# Ampli.net
KiCad netlist of a schematic drawn in Altium Designer
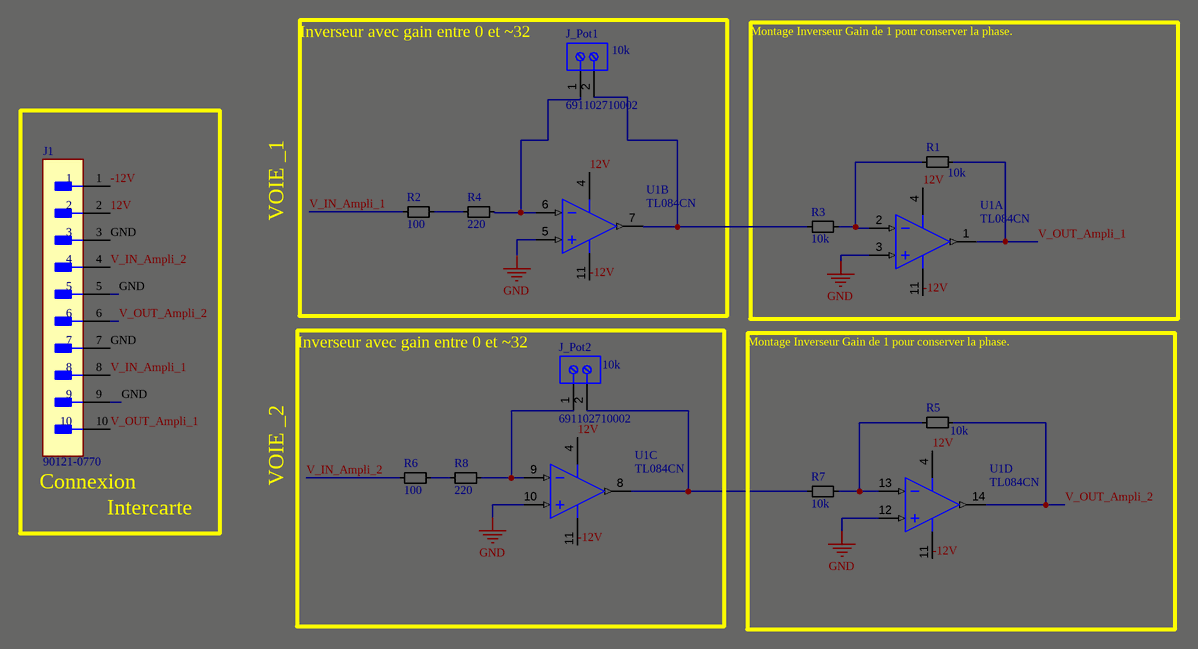
[diagram p0: Ampli.SchDoc]

(export (version "E")
  (design (tool "Eeschema 10.0.6"))
  (components
    (comp (ref "J1")
      (value "90121-0770")
      (footprint "FP-90121-0770-MFG")
      (description "CONN HEADER R/A 10POS 2.54MM")
      (libsource (lib "Altium Content Vault") (part "aee40dc8b284c03a16094555aa210be"))
    )
    (comp (ref "J_Pot1")
      (value "691102710002")
      (footprint "691102710002")
      (fields (field (name "VOLTAGE") "300V"))
      (libsource (lib "Altium Content Vault") (part "TBL - 1R - 02P - Screw"))
    )
    (comp (ref "J_Pot2")
      (value "691102710002")
      (footprint "691102710002")
      (fields (field (name "VOLTAGE") "300V"))
      (libsource (lib "Altium Content Vault") (part "TBL - 1R - 02P - Screw"))
    )
    (comp (ref "R1")
      (value "10k")
      (footprint "PCB:Res_Axial_3.5x6.5mm_TH")
      (fields (field (name "Comment") "Res_3.5x6.5mm_TH"))
      (libsource (lib "Schema") (part "Res_3.5x6.5mm_TH"))
    )
    (comp (ref "R2")
      (value "100")
      (footprint "PCB:Res_Axial_3.5x6.5mm_TH")
      (fields (field (name "Comment") "Res_3.5x6.5mm_TH"))
      (libsource (lib "Schema") (part "Res_3.5x6.5mm_TH"))
    )
    (comp (ref "R3")
      (value "10k")
      (footprint "PCB:Res_Axial_3.5x6.5mm_TH")
      (fields (field (name "Comment") "Res_3.5x6.5mm_TH"))
      (libsource (lib "Schema") (part "Res_3.5x6.5mm_TH"))
    )
    (comp (ref "R4")
      (value "220")
      (footprint "PCB:Res_Axial_3.5x6.5mm_TH")
      (fields (field (name "Comment") "Res_3.5x6.5mm_TH"))
      (libsource (lib "Schema") (part "Res_3.5x6.5mm_TH"))
    )
    (comp (ref "R5")
      (value "10k")
      (footprint "PCB:Res_Axial_3.5x6.5mm_TH")
      (fields (field (name "Comment") "Res_3.5x6.5mm_TH"))
      (libsource (lib "Schema") (part "Res_3.5x6.5mm_TH"))
    )
    (comp (ref "R6")
      (value "100")
      (footprint "PCB:Res_Axial_3.5x6.5mm_TH")
      (fields (field (name "Comment") "Res_3.5x6.5mm_TH"))
      (libsource (lib "Schema") (part "Res_3.5x6.5mm_TH"))
    )
    (comp (ref "R7")
      (value "10k")
      (footprint "PCB:Res_Axial_3.5x6.5mm_TH")
      (fields (field (name "Comment") "Res_3.5x6.5mm_TH"))
      (libsource (lib "Schema") (part "Res_3.5x6.5mm_TH"))
    )
    (comp (ref "R8")
      (value "220")
      (footprint "PCB:Res_Axial_3.5x6.5mm_TH")
      (fields (field (name "Comment") "Res_3.5x6.5mm_TH"))
      (libsource (lib "Schema") (part "Res_3.5x6.5mm_TH"))
    )
    (comp (ref "U1")
      (value "TL084CN")
      (footprint "N0014A")
      (description "JFET-Input Operational Amplifier, 7 to 36 V, 0 to 70 degC, 14-pin DIP (N14), Pb-Free (RoHS)")
      (fields (field (name "MANUFACTURER") "Texas Instruments"))
      (libsource (lib "Altium Content Vault") (part "TI-TLXX4X_MC3403-X14"))
    )
  )
  (nets
    (net (code "1") (name "/-12V") (class "Default")
      (node (ref "J1") (pin "1") (pinfunction "1_1") (pintype "passive"))
      (node (ref "U1") (pin "11") (pinfunction "VCC-_11") (pintype "power_in"))
    )
    (net (code "2") (name "/12V") (class "Default")
      (node (ref "J1") (pin "2") (pinfunction "2_2") (pintype "passive"))
      (node (ref "U1") (pin "4") (pinfunction "VCC+_4") (pintype "power_in"))
    )
    (net (code "3") (name "/V_IN_Ampli_1") (class "Default")
      (node (ref "J1") (pin "8") (pinfunction "8_8") (pintype "passive"))
      (node (ref "R2") (pin "0") (pintype "passive"))
    )
    (net (code "4") (name "/V_IN_Ampli_2") (class "Default")
      (node (ref "J1") (pin "4") (pinfunction "4_4") (pintype "passive"))
      (node (ref "R6") (pin "0") (pintype "passive"))
    )
    (net (code "5") (name "/V_OUT_Ampli_1") (class "Default")
      (node (ref "J1") (pin "10") (pinfunction "10_10") (pintype "passive"))
      (node (ref "R1") (pin "1") (pintype "passive"))
      (node (ref "U1") (pin "1") (pinfunction "OUT1_1") (pintype "output"))
    )
    (net (code "6") (name "/V_OUT_Ampli_2") (class "Default")
      (node (ref "J1") (pin "6") (pinfunction "6_6") (pintype "passive"))
      (node (ref "R5") (pin "1") (pintype "passive"))
      (node (ref "U1") (pin "14") (pinfunction "OUT4_14") (pintype "output"))
    )
    (net (code "7") (name "GND") (class "Default")
      (node (ref "J1") (pin "3") (pinfunction "3_3") (pintype "passive"))
      (node (ref "J1") (pin "5") (pinfunction "5_5") (pintype "passive"))
      (node (ref "J1") (pin "7") (pinfunction "7_7") (pintype "passive"))
      (node (ref "J1") (pin "9") (pinfunction "9_9") (pintype "passive"))
      (node (ref "U1") (pin "10") (pinfunction "IN3+_10") (pintype "input"))
      (node (ref "U1") (pin "12") (pinfunction "IN4+_12") (pintype "input"))
      (node (ref "U1") (pin "3") (pinfunction "IN1+_3") (pintype "input"))
      (node (ref "U1") (pin "5") (pinfunction "IN2+_5") (pintype "input"))
    )
    (net (code "8") (name "Net-(R2-Pad1)") (class "Default")
      (node (ref "R2") (pin "1") (pintype "passive"))
      (node (ref "R4") (pin "0") (pintype "passive"))
    )
    (net (code "9") (name "Net-(R6-Pad1)") (class "Default")
      (node (ref "R6") (pin "1") (pintype "passive"))
      (node (ref "R8") (pin "0") (pintype "passive"))
    )
    (net (code "10") (name "Net-(U1A-IN1-)") (class "Default")
      (node (ref "R1") (pin "0") (pintype "passive"))
      (node (ref "R3") (pin "1") (pintype "passive"))
      (node (ref "U1") (pin "2") (pinfunction "IN1-_2") (pintype "input"))
    )
    (net (code "11") (name "Net-(U1B-IN2-)") (class "Default")
      (node (ref "J_Pot1") (pin "1") (pinfunction "1_1") (pintype "passive"))
      (node (ref "R4") (pin "1") (pintype "passive"))
      (node (ref "U1") (pin "6") (pinfunction "IN2-_6") (pintype "input"))
    )
    (net (code "12") (name "Net-(U1B-OUT2)") (class "Default")
      (node (ref "J_Pot1") (pin "2") (pinfunction "2_2") (pintype "passive"))
      (node (ref "R3") (pin "0") (pintype "passive"))
      (node (ref "U1") (pin "7") (pinfunction "OUT2_7") (pintype "output"))
    )
    (net (code "13") (name "Net-(U1C-IN3-)") (class "Default")
      (node (ref "J_Pot2") (pin "1") (pinfunction "1_1") (pintype "passive"))
      (node (ref "R8") (pin "1") (pintype "passive"))
      (node (ref "U1") (pin "9") (pinfunction "IN3-_9") (pintype "input"))
    )
    (net (code "14") (name "Net-(U1C-OUT3)") (class "Default")
      (node (ref "J_Pot2") (pin "2") (pinfunction "2_2") (pintype "passive"))
      (node (ref "R7") (pin "0") (pintype "passive"))
      (node (ref "U1") (pin "8") (pinfunction "OUT3_8") (pintype "output"))
    )
    (net (code "15") (name "Net-(U1D-IN4-)") (class "Default")
      (node (ref "R5") (pin "0") (pintype "passive"))
      (node (ref "R7") (pin "1") (pintype "passive"))
      (node (ref "U1") (pin "13") (pinfunction "IN4-_13") (pintype "input"))
    )
  )
)
